# LMP848x_Breakout_v1_1.net
KiCad netlist of a schematic drawn in EAGLE
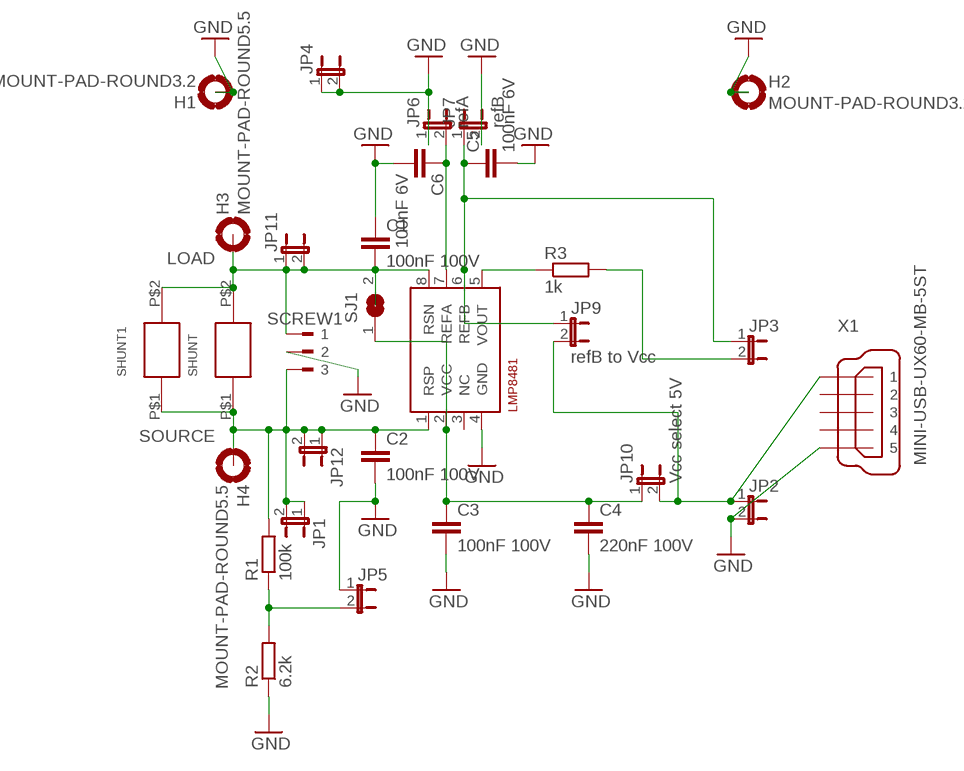
[diagram p0: schematic, sheet 1]

(export (version "E")
  (design (tool "Eeschema 10.0.6"))
  (components
    (comp (ref "C1")
      (value "100nF 100V")
      (footprint "eagle-import:C0805")
      (libsource (lib "eagle-import") (part "C-EUC0805"))
    )
    (comp (ref "C2")
      (value "100nF 100V")
      (footprint "eagle-import:C0805")
      (libsource (lib "eagle-import") (part "C-EUC0805"))
    )
    (comp (ref "C3")
      (value "100nF 100V")
      (footprint "eagle-import:C0805")
      (libsource (lib "eagle-import") (part "C-EUC0805"))
    )
    (comp (ref "C4")
      (value "220nF 100V")
      (footprint "eagle-import:C0805")
      (libsource (lib "eagle-import") (part "C-EUC0805"))
    )
    (comp (ref "C5")
      (value "100nF 6V")
      (footprint "eagle-import:C0805")
      (libsource (lib "eagle-import") (part "C-EUC0805"))
    )
    (comp (ref "C6")
      (value "100nF 6V")
      (footprint "eagle-import:C0805")
      (libsource (lib "eagle-import") (part "C-EUC0805"))
    )
    (comp (ref "H1")
      (value "MOUNT-PAD-ROUND3.2")
      (footprint "eagle-import:3,2-PAD")
      (libsource (lib "eagle-import") (part "MOUNT-PAD-ROUND3.2"))
    )
    (comp (ref "H2")
      (value "MOUNT-PAD-ROUND3.2")
      (footprint "eagle-import:3,2-PAD")
      (libsource (lib "eagle-import") (part "MOUNT-PAD-ROUND3.2"))
    )
    (comp (ref "H3")
      (value "MOUNT-PAD-ROUND5.5")
      (footprint "eagle-import:5,5-PAD")
      (libsource (lib "eagle-import") (part "MOUNT-PAD-ROUND5.5"))
    )
    (comp (ref "H4")
      (value "MOUNT-PAD-ROUND5.5")
      (footprint "eagle-import:5,5-PAD")
      (libsource (lib "eagle-import") (part "MOUNT-PAD-ROUND5.5"))
    )
    (comp (ref "JP1")
      (value "JP1E")
      (footprint "eagle-import:JP1")
      (libsource (lib "eagle-import") (part "JP1E"))
    )
    (comp (ref "JP2")
      (value "JP1E")
      (footprint "eagle-import:JP1")
      (libsource (lib "eagle-import") (part "JP1E"))
    )
    (comp (ref "JP3")
      (value "JP1E")
      (footprint "eagle-import:JP1")
      (libsource (lib "eagle-import") (part "JP1E"))
    )
    (comp (ref "JP4")
      (value "JP1E")
      (footprint "eagle-import:JP1")
      (libsource (lib "eagle-import") (part "JP1E"))
    )
    (comp (ref "JP5")
      (value "JP1E")
      (footprint "eagle-import:JP1")
      (libsource (lib "eagle-import") (part "JP1E"))
    )
    (comp (ref "JP6")
      (value "refA")
      (footprint "eagle-import:JP1")
      (libsource (lib "eagle-import") (part "JP1E"))
    )
    (comp (ref "JP7")
      (value "refB")
      (footprint "eagle-import:JP1")
      (libsource (lib "eagle-import") (part "JP1E"))
    )
    (comp (ref "JP9")
      (value "refB to Vcc")
      (footprint "eagle-import:JP1")
      (libsource (lib "eagle-import") (part "JP1E"))
    )
    (comp (ref "JP10")
      (value "Vcc select 5V")
      (footprint "eagle-import:JP1")
      (libsource (lib "eagle-import") (part "JP1E"))
    )
    (comp (ref "JP11")
      (value "JP1E")
      (footprint "eagle-import:JP1")
      (libsource (lib "eagle-import") (part "JP1E"))
    )
    (comp (ref "JP12")
      (value "JP1E")
      (footprint "eagle-import:JP1")
      (libsource (lib "eagle-import") (part "JP1E"))
    )
    (comp (ref "LMP8481")
      (value "LMP8481-H")
      (footprint "eagle-import:S-PDSO-G08")
      (libsource (lib "eagle-import") (part "LMP8481-H"))
    )
    (comp (ref "R1")
      (value "100k")
      (footprint "eagle-import:0207_7")
      (libsource (lib "eagle-import") (part "R-EU_0207/7"))
    )
    (comp (ref "R2")
      (value "6.2k")
      (footprint "eagle-import:0207_7")
      (libsource (lib "eagle-import") (part "R-EU_0207/7"))
    )
    (comp (ref "R3")
      (value "1k")
      (footprint "eagle-import:0204_5")
      (libsource (lib "eagle-import") (part "R-EU_0204/5"))
    )
    (comp (ref "SCREW1")
      (value "180-3")
      (footprint "eagle-import:180-3")
      (libsource (lib "eagle-import") (part "180-3"))
    )
    (comp (ref "SHUNT")
      (value "EBW_SERIES_15.2MM")
      (footprint "eagle-import:EBW_SERIES_15.2MM")
      (libsource (lib "eagle-import") (part "EBW_SERIES_15.2MM"))
    )
    (comp (ref "SHUNT1")
      (value "EBW_SERIES_15.2MM")
      (footprint "eagle-import:EBW_SERIES_15.2MM")
      (libsource (lib "eagle-import") (part "EBW_SERIES_15.2MM"))
    )
    (comp (ref "SJ1") (value "SJ") (footprint "eagle-import:SJ") (libsource (lib "eagle-import") (part "SJ")))
    (comp (ref "X1")
      (value "MINI-USB-UX60-MB-5ST")
      (footprint "eagle-import:UX60-MB-5ST")
      (libsource (lib "eagle-import") (part "MINI-USB-UX60-MB-5ST"))
    )
  )
  (nets
    (net (code "1") (name "/LOAD") (class "Default")
      (node (ref "C1") (pin "2") (pinfunction "2_2") (pintype "passive"))
      (node (ref "H3") (pin "B5,5") (pinfunction "MOUNT_B5,5") (pintype "passive"))
      (node (ref "JP11") (pin "1") (pinfunction "1_1") (pintype "passive"))
      (node (ref "JP11") (pin "2") (pinfunction "2_2") (pintype "passive"))
      (node (ref "LMP8481") (pin "8") (pinfunction "RSN_8") (pintype "bidirectional"))
      (node (ref "SCREW1") (pin "1") (pinfunction "1_1") (pintype "passive"))
      (node (ref "SHUNT") (pin "P$2") (pinfunction "P$2_P$2") (pintype "bidirectional"))
      (node (ref "SHUNT1") (pin "P$2") (pinfunction "P$2_P$2") (pintype "bidirectional"))
      (node (ref "SJ1") (pin "2") (pinfunction "2_2") (pintype "passive"))
    )
    (net (code "2") (name "/SOURCE") (class "Default")
      (node (ref "C2") (pin "1") (pinfunction "1_1") (pintype "passive"))
      (node (ref "H4") (pin "B5,5") (pinfunction "MOUNT_B5,5") (pintype "passive"))
      (node (ref "JP1") (pin "1") (pinfunction "1_1") (pintype "passive"))
      (node (ref "JP1") (pin "2") (pinfunction "2_2") (pintype "passive"))
      (node (ref "JP12") (pin "1") (pinfunction "1_1") (pintype "passive"))
      (node (ref "JP12") (pin "2") (pinfunction "2_2") (pintype "passive"))
      (node (ref "LMP8481") (pin "1") (pinfunction "RSP_1") (pintype "bidirectional"))
      (node (ref "R1") (pin "2") (pinfunction "2_2") (pintype "passive"))
      (node (ref "SCREW1") (pin "3") (pinfunction "3_3") (pintype "passive"))
      (node (ref "SHUNT") (pin "P$1") (pinfunction "P$1_P$1") (pintype "bidirectional"))
      (node (ref "SHUNT1") (pin "P$1") (pinfunction "P$1_P$1") (pintype "bidirectional"))
    )
    (net (code "3") (name "GND") (class "Default")
      (node (ref "C1") (pin "1") (pinfunction "1_1") (pintype "passive"))
      (node (ref "C2") (pin "2") (pinfunction "2_2") (pintype "passive"))
      (node (ref "C3") (pin "2") (pinfunction "2_2") (pintype "passive"))
      (node (ref "C4") (pin "2") (pinfunction "2_2") (pintype "passive"))
      (node (ref "C5") (pin "2") (pinfunction "2_2") (pintype "passive"))
      (node (ref "C6") (pin "2") (pinfunction "2_2") (pintype "passive"))
      (node (ref "H1") (pin "B3,2") (pinfunction "MOUNT_B3,2") (pintype "passive"))
      (node (ref "H2") (pin "B3,2") (pinfunction "MOUNT_B3,2") (pintype "passive"))
      (node (ref "JP2") (pin "2") (pinfunction "2_2") (pintype "passive"))
      (node (ref "JP4") (pin "1") (pinfunction "1_1") (pintype "passive"))
      (node (ref "JP4") (pin "2") (pinfunction "2_2") (pintype "passive"))
      (node (ref "JP5") (pin "1") (pinfunction "1_1") (pintype "passive"))
      (node (ref "JP6") (pin "1") (pinfunction "1_1") (pintype "passive"))
      (node (ref "JP7") (pin "2") (pinfunction "2_2") (pintype "passive"))
      (node (ref "LMP8481") (pin "4") (pinfunction "GND_4") (pintype "bidirectional"))
      (node (ref "R2") (pin "1") (pinfunction "1_1") (pintype "passive"))
      (node (ref "SCREW1") (pin "2") (pinfunction "2_2") (pintype "passive"))
      (node (ref "X1") (pin "5") (pinfunction "5_5") (pintype "input"))
    )
    (net (code "4") (name "Net-(JP3-Pad2)") (class "Default")
      (node (ref "JP3") (pin "2") (pinfunction "2_2") (pintype "passive"))
      (node (ref "R3") (pin "2") (pinfunction "2_2") (pintype "passive"))
    )
    (net (code "5") (name "Net-(JP5-Pad2)") (class "Default")
      (node (ref "JP5") (pin "2") (pinfunction "2_2") (pintype "passive"))
      (node (ref "R1") (pin "1") (pinfunction "1_1") (pintype "passive"))
      (node (ref "R2") (pin "2") (pinfunction "2_2") (pintype "passive"))
    )
    (net (code "6") (name "Net-(JP10-Pad2)") (class "Default")
      (node (ref "JP10") (pin "2") (pinfunction "2_2") (pintype "passive"))
      (node (ref "JP2") (pin "1") (pinfunction "1_1") (pintype "passive"))
      (node (ref "JP9") (pin "2") (pinfunction "2_2") (pintype "passive"))
      (node (ref "X1") (pin "1") (pinfunction "1_1") (pintype "input"))
    )
    (net (code "7") (name "Net-(LMP8481-REFA)") (class "Default")
      (node (ref "C6") (pin "1") (pinfunction "1_1") (pintype "passive"))
      (node (ref "JP6") (pin "2") (pinfunction "2_2") (pintype "passive"))
      (node (ref "LMP8481") (pin "7") (pinfunction "REFA_7") (pintype "bidirectional"))
    )
    (net (code "8") (name "Net-(LMP8481-REFB)") (class "Default")
      (node (ref "C5") (pin "1") (pinfunction "1_1") (pintype "passive"))
      (node (ref "JP3") (pin "1") (pinfunction "1_1") (pintype "passive"))
      (node (ref "JP7") (pin "1") (pinfunction "1_1") (pintype "passive"))
      (node (ref "JP9") (pin "1") (pinfunction "1_1") (pintype "passive"))
      (node (ref "LMP8481") (pin "6") (pinfunction "REFB_6") (pintype "bidirectional"))
    )
    (net (code "9") (name "Net-(LMP8481-VCC)") (class "Default")
      (node (ref "C3") (pin "1") (pinfunction "1_1") (pintype "passive"))
      (node (ref "C4") (pin "1") (pinfunction "1_1") (pintype "passive"))
      (node (ref "JP10") (pin "1") (pinfunction "1_1") (pintype "passive"))
      (node (ref "LMP8481") (pin "2") (pinfunction "VCC_2") (pintype "bidirectional"))
      (node (ref "SJ1") (pin "1") (pinfunction "1_1") (pintype "passive"))
    )
    (net (code "10") (name "Net-(LMP8481-VOUT)") (class "Default")
      (node (ref "LMP8481") (pin "5") (pinfunction "VOUT_5") (pintype "bidirectional"))
      (node (ref "R3") (pin "1") (pinfunction "1_1") (pintype "passive"))
    )
    (net (code "11") (name "unconnected-(LMP8481-NC-Pad3)") (class "Default")
      (node (ref "LMP8481") (pin "3") (pinfunction "NC_3") (pintype "bidirectional"))
    )
    (net (code "12") (name "unconnected-(X1-Pad2)") (class "Default")
      (node (ref "X1") (pin "2") (pinfunction "2_2") (pintype "input"))
    )
    (net (code "13") (name "unconnected-(X1-Pad3)") (class "Default")
      (node (ref "X1") (pin "3") (pinfunction "3_3") (pintype "input"))
    )
    (net (code "14") (name "unconnected-(X1-Pad4)") (class "Default")
      (node (ref "X1") (pin "4") (pinfunction "4_4") (pintype "input"))
    )
  )
)
